# DFTT.net
KiCad netlist of a schematic drawn in EAGLE
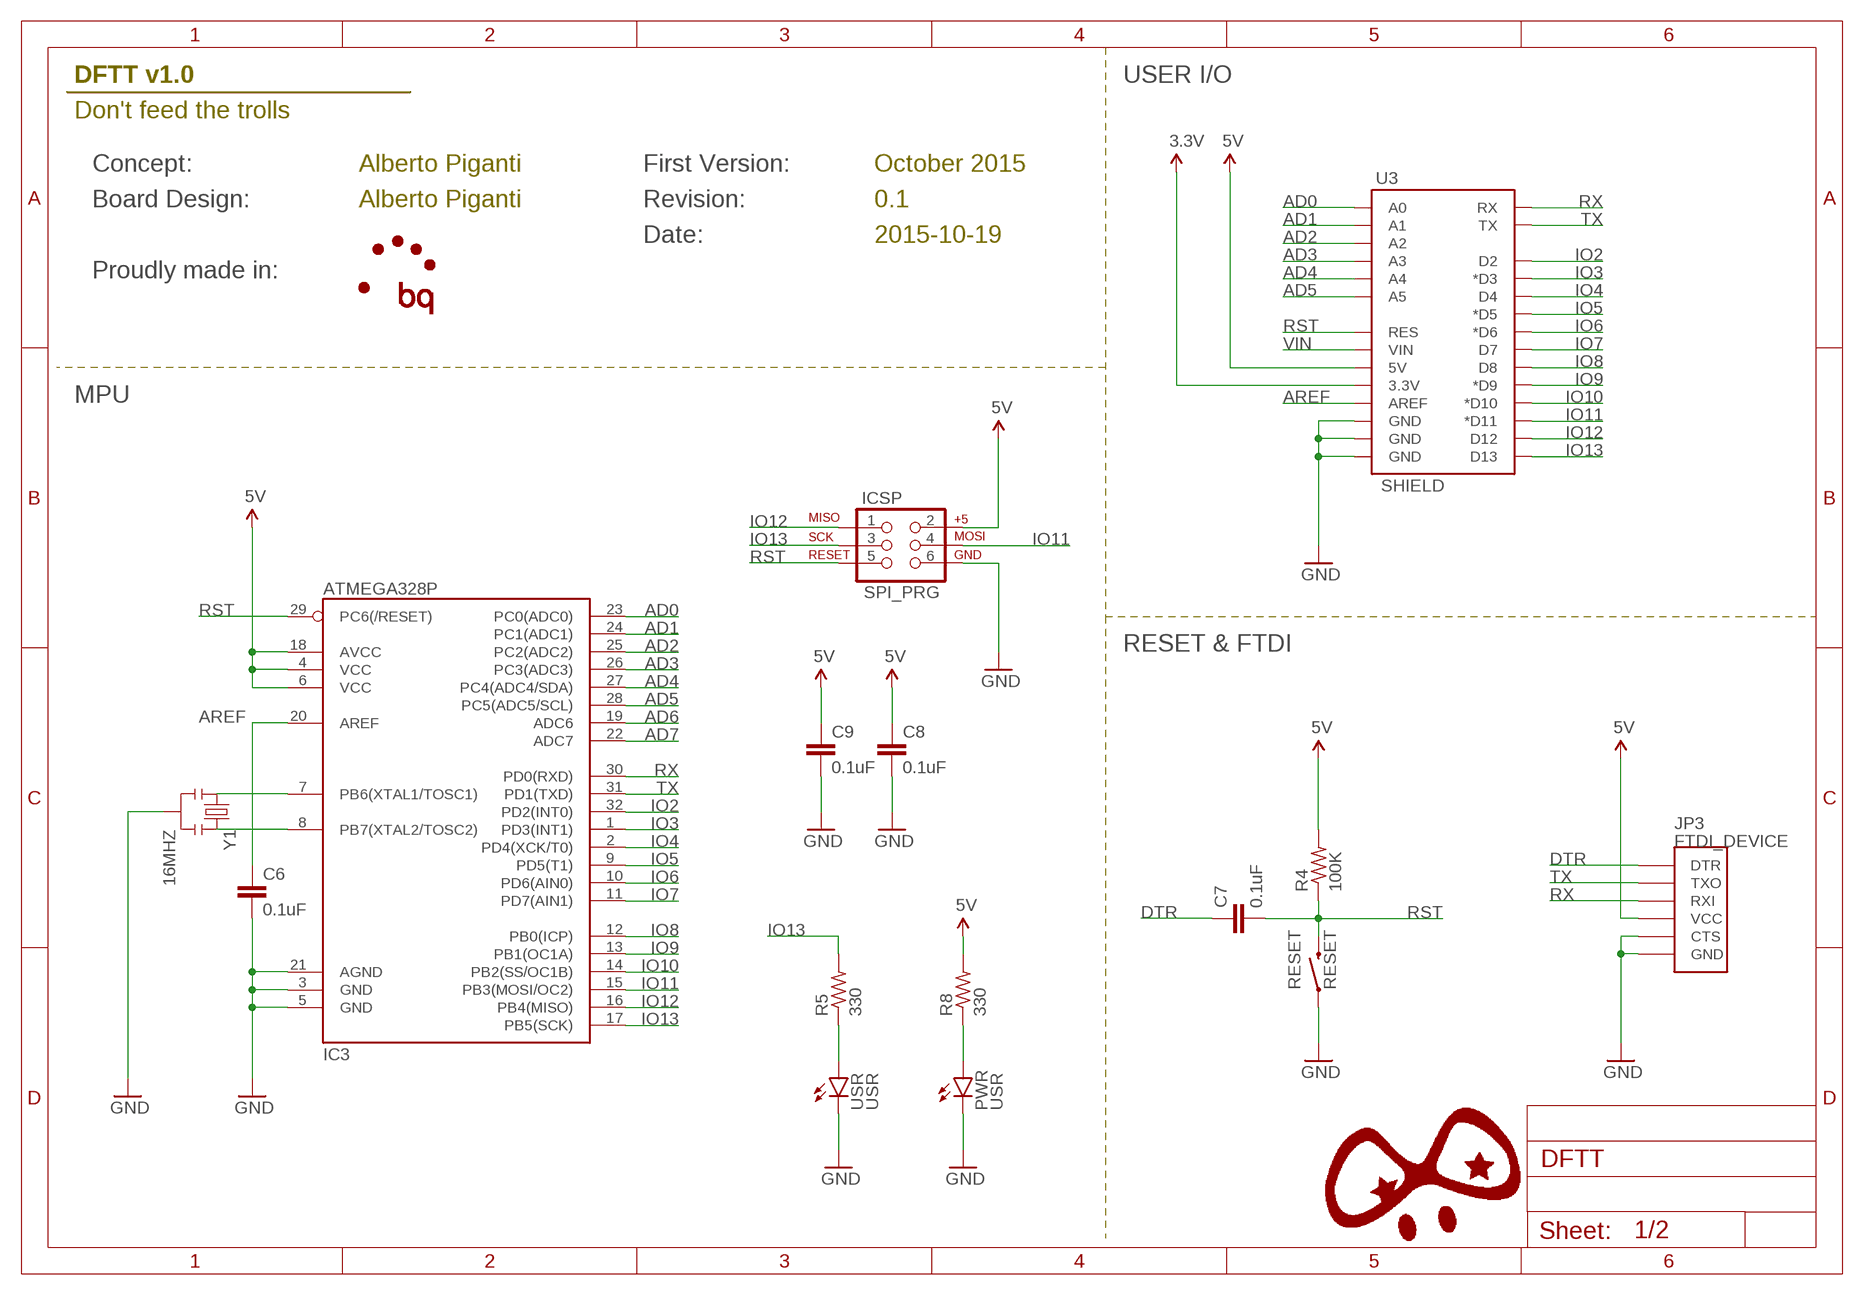
[diagram p0: schematic, sheet 1]
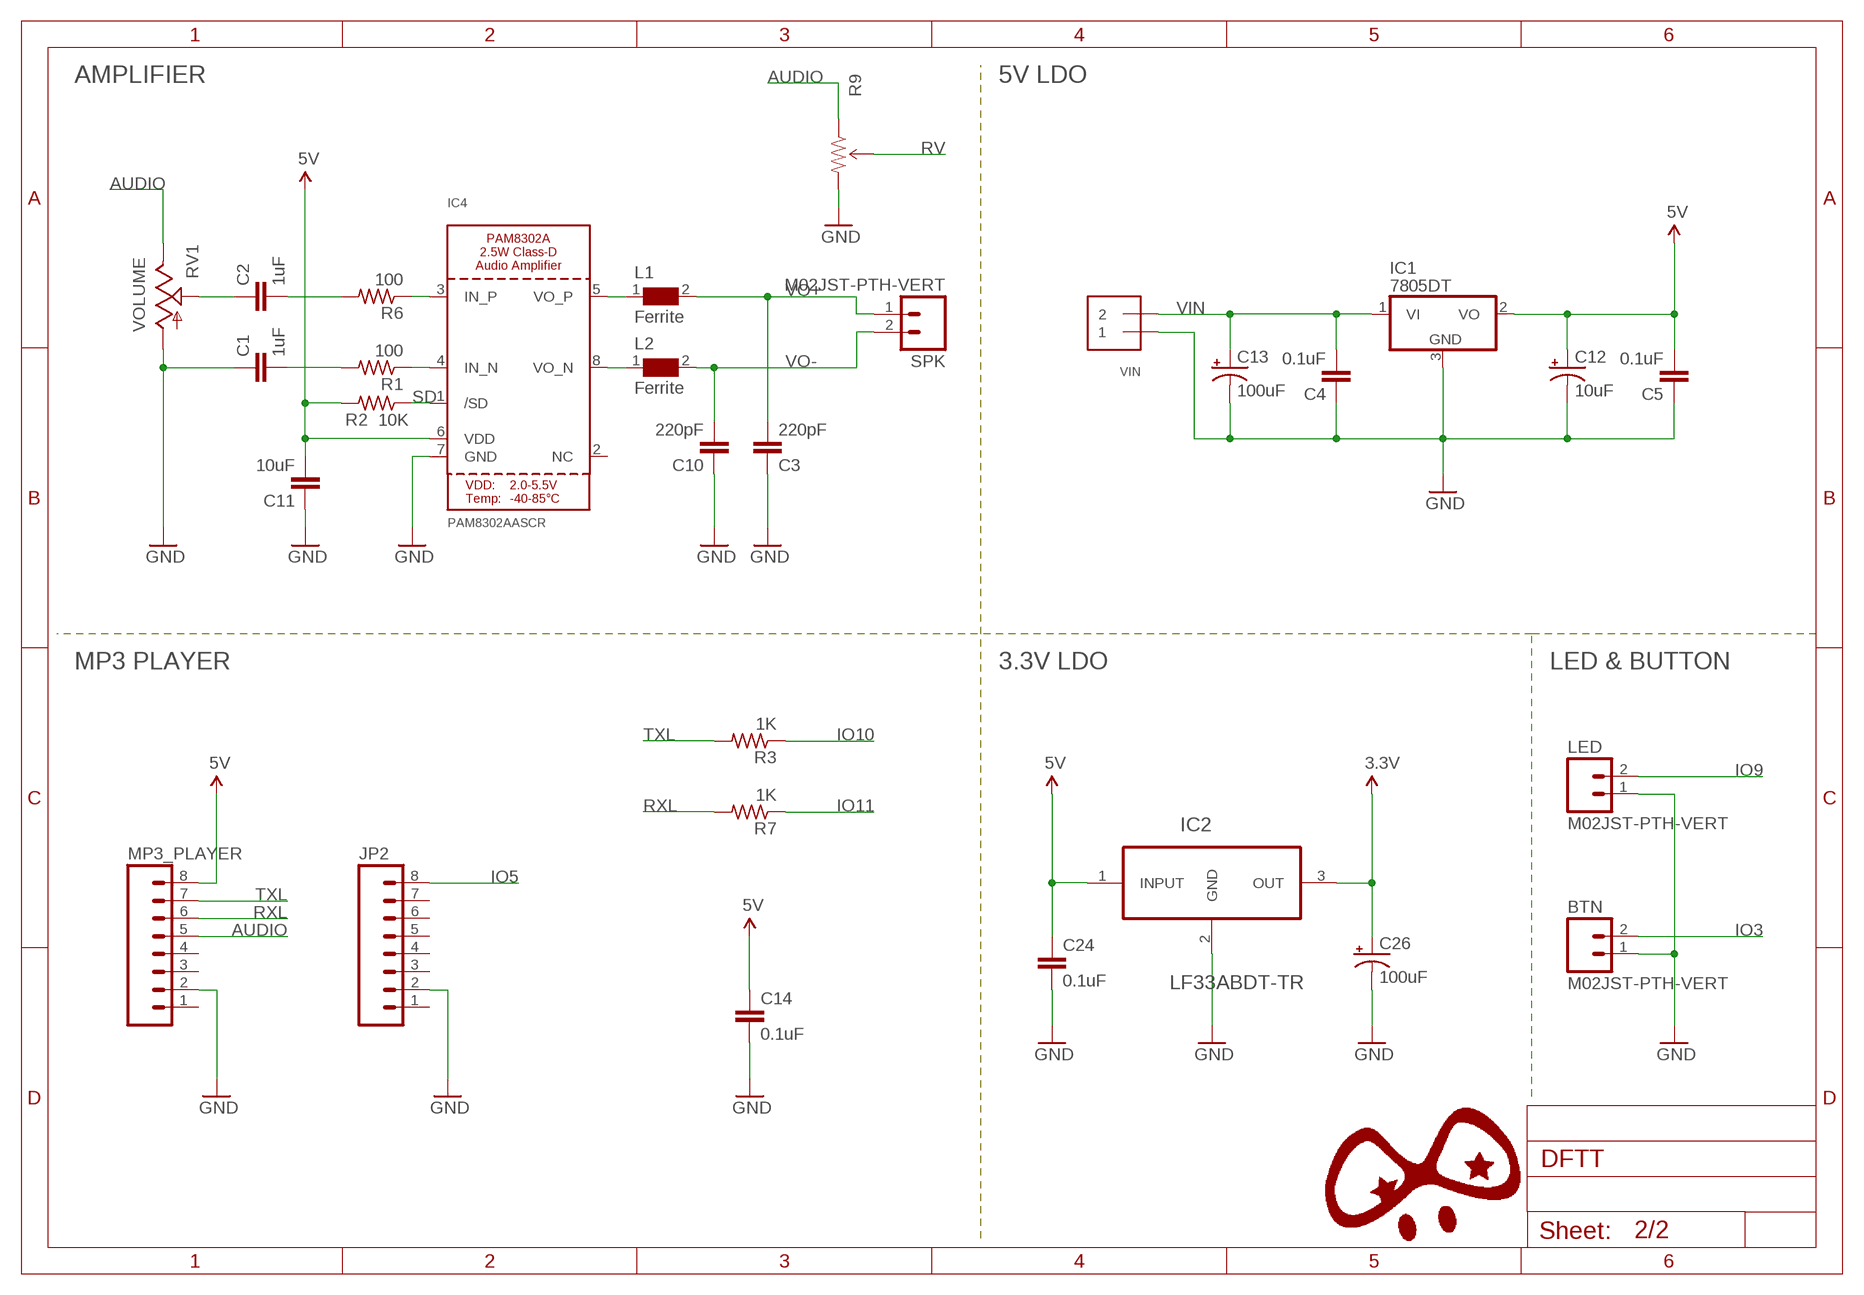
[diagram p1: schematic, sheet 2]

(export (version "E")
  (design (tool "Eeschema 10.0.6"))
  (components
    (comp (ref "BTN")
      (value "M02JST-PTH-VERT")
      (footprint "eagle-import:JST-2-PTH-VERT")
      (libsource (lib "eagle-import") (part "M02JST-PTH-VERT"))
    )
    (comp (ref "C1")
      (value "1uF")
      (footprint "eagle-import:C0603")
      (libsource (lib "eagle-import") (part "C-EUC0603"))
    )
    (comp (ref "C2")
      (value "1uF")
      (footprint "eagle-import:C0603")
      (libsource (lib "eagle-import") (part "C-EUC0603"))
    )
    (comp (ref "C3")
      (value "220pF")
      (footprint "eagle-import:C0603")
      (libsource (lib "eagle-import") (part "C-EUC0603"))
    )
    (comp (ref "C4")
      (value "0.1uF")
      (footprint "eagle-import:C0603")
      (libsource (lib "eagle-import") (part "C-EUC0603"))
    )
    (comp (ref "C5")
      (value "0.1uF")
      (footprint "eagle-import:C0603")
      (libsource (lib "eagle-import") (part "C-EUC0603"))
    )
    (comp (ref "C10")
      (value "220pF")
      (footprint "eagle-import:C0603")
      (libsource (lib "eagle-import") (part "C-EUC0603"))
    )
    (comp (ref "C11")
      (value "10uF")
      (footprint "eagle-import:C0603")
      (libsource (lib "eagle-import") (part "C-EUC0603"))
    )
    (comp (ref "C12")
      (value "10uF")
      (footprint "eagle-import:PANASONIC_D")
      (libsource (lib "eagle-import") (part "CAP_POLD"))
    )
    (comp (ref "C13")
      (value "100uF")
      (footprint "eagle-import:PANASONIC_D")
      (libsource (lib "eagle-import") (part "CAP_POLD"))
    )
    (comp (ref "C14")
      (value "0.1uF")
      (footprint "eagle-import:1210")
      (libsource (lib "eagle-import") (part "CAP1210"))
    )
    (comp (ref "C24")
      (value "0.1uF")
      (footprint "eagle-import:1210")
      (libsource (lib "eagle-import") (part "CAP1210"))
    )
    (comp (ref "C26")
      (value "100uF")
      (footprint "eagle-import:PANASONIC_D")
      (libsource (lib "eagle-import") (part "CAP_POLD"))
    )
    (comp (ref "IC1")
      (value "7805DT")
      (footprint "eagle-import:TO252")
      (libsource (lib "eagle-import") (part "78DT05"))
    )
    (comp (ref "IC2")
      (value "LF33ABDT-TR")
      (footprint "eagle-import:TO228P972X240-3N")
      (libsource (lib "eagle-import") (part "LF33ABDT-TR"))
    )
    (comp (ref "IC4")
      (value "PAM8302AASCR")
      (footprint "eagle-import:MSOP8_0.65MM")
      (libsource (lib "eagle-import") (part "AUDIOAMP_PAM8302A"))
    )
    (comp (ref "JP2")
      (value "M08LOCK")
      (footprint "eagle-import:1X08_LOCK")
      (libsource (lib "eagle-import") (part "M08LOCK"))
    )
    (comp (ref "L1")
      (value "Ferrite")
      (footprint "eagle-import:0603")
      (fields (field (name "MPN") "74279261"))
      (libsource (lib "eagle-import") (part "FERRITE_0603-74279261"))
    )
    (comp (ref "L2")
      (value "Ferrite")
      (footprint "eagle-import:0603")
      (fields (field (name "MPN") "74279261"))
      (libsource (lib "eagle-import") (part "FERRITE_0603-74279261"))
    )
    (comp (ref "LED")
      (value "M02JST-PTH-VERT")
      (footprint "eagle-import:JST-2-PTH-VERT")
      (libsource (lib "eagle-import") (part "M02JST-PTH-VERT"))
    )
    (comp (ref "MP3_PLAYER")
      (value "M08LOCK")
      (footprint "eagle-import:1X08_LOCK")
      (libsource (lib "eagle-import") (part "M08LOCK"))
    )
    (comp (ref "R1")
      (value "100")
      (footprint "eagle-import:R0603")
      (libsource (lib "eagle-import") (part "R-US_R0603"))
    )
    (comp (ref "R2")
      (value "10K")
      (footprint "eagle-import:R0603")
      (libsource (lib "eagle-import") (part "R-US_R0603"))
    )
    (comp (ref "R3")
      (value "1K")
      (footprint "eagle-import:R0603")
      (libsource (lib "eagle-import") (part "R-US_R0603"))
    )
    (comp (ref "R6")
      (value "100")
      (footprint "eagle-import:R0603")
      (libsource (lib "eagle-import") (part "R-US_R0603"))
    )
    (comp (ref "R7")
      (value "1K")
      (footprint "eagle-import:R0603")
      (libsource (lib "eagle-import") (part "R-US_R0603"))
    )
    (comp (ref "R9")
      (value "TRIMPOT3362U-2")
      (footprint "eagle-import:3362U-2")
      (libsource (lib "eagle-import") (part "TRIMPOT3362U-2"))
    )
    (comp (ref "RV1")
      (value "VOLUME")
      (footprint "eagle-import:TRIM_POT")
      (libsource (lib "eagle-import") (part "POTTRIM"))
    )
    (comp (ref "SPK")
      (value "M02JST-PTH-VERT")
      (footprint "eagle-import:JST-2-PTH-VERT")
      (libsource (lib "eagle-import") (part "M02JST-PTH-VERT"))
    )
    (comp (ref "VIN")
      (value "TERMBLOCK_1X2")
      (footprint "eagle-import:TERMBLOCK_1X2-3.5MM")
      (libsource (lib "eagle-import") (part "TERMBLOCK_1X2"))
    )
    (comp (ref "C6")
      (value "0.1uF")
      (footprint "eagle-import:C0603")
      (libsource (lib "eagle-import") (part "C-EUC0603"))
    )
    (comp (ref "C7")
      (value "0.1uF")
      (footprint "eagle-import:C0603")
      (libsource (lib "eagle-import") (part "C-EUC0603"))
    )
    (comp (ref "C8")
      (value "0.1uF")
      (footprint "eagle-import:C0603")
      (libsource (lib "eagle-import") (part "C-EUC0603"))
    )
    (comp (ref "C9")
      (value "0.1uF")
      (footprint "eagle-import:C0603")
      (libsource (lib "eagle-import") (part "C-EUC0603"))
    )
    (comp (ref "IC3")
      (value "ATMEGA328P")
      (footprint "eagle-import:TQFP32-08")
      (libsource (lib "eagle-import") (part "ATMEGA328_SMT"))
    )
    (comp (ref "ICSP")
      (value "SPI_PRG")
      (footprint "eagle-import:2X3-NS")
      (libsource (lib "eagle-import") (part "AVR_SPI_PRG_6NS"))
    )
    (comp (ref "JP3")
      (value "FTDI_DEVICE")
      (footprint "eagle-import:FTDI_DEVICE_SIDE")
      (libsource (lib "eagle-import") (part "FTDI_DEVICE"))
    )
    (comp (ref "PWR")
      (value "USR")
      (footprint "eagle-import:LED-0603")
      (libsource (lib "eagle-import") (part "LED0603"))
    )
    (comp (ref "R4")
      (value "100K")
      (footprint "eagle-import:R0603")
      (libsource (lib "eagle-import") (part "R-US_R0603"))
    )
    (comp (ref "R5")
      (value "330")
      (footprint "eagle-import:R0603")
      (libsource (lib "eagle-import") (part "R-US_R0603"))
    )
    (comp (ref "R8")
      (value "330")
      (footprint "eagle-import:R0603")
      (libsource (lib "eagle-import") (part "R-US_R0603"))
    )
    (comp (ref "RESET")
      (value "RESET")
      (footprint "eagle-import:TACTILE-SWITCH-1101NE")
      (libsource (lib "eagle-import") (part "SWITCH-MOMENTARY-2SMD-1101NE"))
    )
    (comp (ref "U3")
      (value "SHIELD")
      (footprint "eagle-import:DUEMILANOVE_VIAS")
      (libsource (lib "eagle-import") (part "ARDUINO_SHIELDNO_SILK"))
    )
    (comp (ref "USR")
      (value "USR")
      (footprint "eagle-import:LED-0603")
      (libsource (lib "eagle-import") (part "LED0603"))
    )
    (comp (ref "Y1")
      (value "16MHZ")
      (footprint "eagle-import:RESONATOR-SMD")
      (libsource (lib "eagle-import") (part "RESONATOR16MHZ"))
    )
  )
  (nets
    (net (code "1") (name "3.3V") (class "Default")
      (node (ref "C26") (pin "+") (pinfunction "+_+") (pintype "passive"))
      (node (ref "IC2") (pin "3") (pinfunction "OUT_3") (pintype "output"))
      (node (ref "U3") (pin "3.3V") (pinfunction "3.3V_3.3V") (pintype "bidirectional"))
    )
    (net (code "2") (name "5V") (class "Default")
      (node (ref "C11") (pin "2") (pinfunction "2_2") (pintype "passive"))
      (node (ref "C12") (pin "+") (pinfunction "+_+") (pintype "passive"))
      (node (ref "C14") (pin "1") (pinfunction "1_1") (pintype "passive"))
      (node (ref "C24") (pin "1") (pinfunction "1_1") (pintype "passive"))
      (node (ref "C5") (pin "2") (pinfunction "2_2") (pintype "passive"))
      (node (ref "C8") (pin "1") (pinfunction "1_1") (pintype "passive"))
      (node (ref "C9") (pin "1") (pinfunction "1_1") (pintype "passive"))
      (node (ref "IC1") (pin "2") (pinfunction "VO_2") (pintype "passive"))
      (node (ref "IC2") (pin "1") (pinfunction "INPUT_1") (pintype "input"))
      (node (ref "IC3") (pin "18") (pinfunction "AVCC_18") (pintype "bidirectional"))
      (node (ref "IC3") (pin "4") (pinfunction "VCC_4") (pintype "bidirectional"))
      (node (ref "IC3") (pin "6") (pinfunction "VCC_6") (pintype "bidirectional"))
      (node (ref "IC4") (pin "6") (pinfunction "VDD_6") (pintype "power_in"))
      (node (ref "ICSP") (pin "2") (pinfunction "2_2") (pintype "passive"))
      (node (ref "JP3") (pin "P$4") (pinfunction "VCC_P$4") (pintype "bidirectional"))
      (node (ref "MP3_PLAYER") (pin "8") (pinfunction "8_8") (pintype "passive"))
      (node (ref "R2") (pin "2") (pinfunction "2_2") (pintype "passive"))
      (node (ref "R4") (pin "2") (pinfunction "2_2") (pintype "passive"))
      (node (ref "R8") (pin "2") (pinfunction "2_2") (pintype "passive"))
      (node (ref "U3") (pin "5V") (pinfunction "5V_5V") (pintype "bidirectional"))
    )
    (net (code "3") (name "AD0") (class "Default")
      (node (ref "IC3") (pin "23") (pinfunction "PC0(ADC0)_23") (pintype "bidirectional"))
      (node (ref "U3") (pin "A0") (pinfunction "A0_A0") (pintype "bidirectional"))
    )
    (net (code "4") (name "AD1") (class "Default")
      (node (ref "IC3") (pin "24") (pinfunction "PC1(ADC1)_24") (pintype "bidirectional"))
      (node (ref "U3") (pin "A1") (pinfunction "A1_A1") (pintype "bidirectional"))
    )
    (net (code "5") (name "AD2") (class "Default")
      (node (ref "IC3") (pin "25") (pinfunction "PC2(ADC2)_25") (pintype "bidirectional"))
      (node (ref "U3") (pin "A2") (pinfunction "A2_A2") (pintype "bidirectional"))
    )
    (net (code "6") (name "AD3") (class "Default")
      (node (ref "IC3") (pin "26") (pinfunction "PC3(ADC3)_26") (pintype "bidirectional"))
      (node (ref "U3") (pin "A3") (pinfunction "A3_A3") (pintype "bidirectional"))
    )
    (net (code "7") (name "AD4") (class "Default")
      (node (ref "IC3") (pin "27") (pinfunction "PC4(ADC4/SDA)_27") (pintype "bidirectional"))
      (node (ref "U3") (pin "A4") (pinfunction "A4_A4") (pintype "bidirectional"))
    )
    (net (code "8") (name "AD5") (class "Default")
      (node (ref "IC3") (pin "28") (pinfunction "PC5(ADC5/SCL)_28") (pintype "bidirectional"))
      (node (ref "U3") (pin "A5") (pinfunction "A5_A5") (pintype "bidirectional"))
    )
    (net (code "9") (name "AD6") (class "Default")
      (node (ref "IC3") (pin "19") (pinfunction "ADC6_19") (pintype "bidirectional"))
    )
    (net (code "10") (name "AD7") (class "Default")
      (node (ref "IC3") (pin "22") (pinfunction "ADC7_22") (pintype "bidirectional"))
    )
    (net (code "11") (name "AREF") (class "Default")
      (node (ref "C6") (pin "1") (pinfunction "1_1") (pintype "passive"))
      (node (ref "IC3") (pin "20") (pinfunction "AREF_20") (pintype "bidirectional"))
      (node (ref "U3") (pin "AREF") (pinfunction "AREF_AREF") (pintype "bidirectional"))
    )
    (net (code "12") (name "AUDIO") (class "Default")
      (node (ref "MP3_PLAYER") (pin "5") (pinfunction "5_5") (pintype "passive"))
      (node (ref "R9") (pin "1") (pinfunction "CCW_1") (pintype "passive"))
      (node (ref "RV1") (pin "2") (pinfunction "E_2") (pintype "passive"))
    )
    (net (code "13") (name "DTR") (class "Default")
      (node (ref "C7") (pin "1") (pinfunction "1_1") (pintype "passive"))
      (node (ref "JP3") (pin "P$1") (pinfunction "DTR_P$1") (pintype "bidirectional"))
    )
    (net (code "14") (name "GND") (class "Default")
      (node (ref "BTN") (pin "1") (pinfunction "1_1") (pintype "passive"))
      (node (ref "C1") (pin "1") (pinfunction "1_1") (pintype "passive"))
      (node (ref "C10") (pin "1") (pinfunction "1_1") (pintype "passive"))
      (node (ref "C11") (pin "1") (pinfunction "1_1") (pintype "passive"))
      (node (ref "C12") (pin "-") (pinfunction "-_-") (pintype "passive"))
      (node (ref "C13") (pin "-") (pinfunction "-_-") (pintype "passive"))
      (node (ref "C14") (pin "2") (pinfunction "2_2") (pintype "passive"))
      (node (ref "C24") (pin "2") (pinfunction "2_2") (pintype "passive"))
      (node (ref "C26") (pin "-") (pinfunction "-_-") (pintype "passive"))
      (node (ref "C3") (pin "1") (pinfunction "1_1") (pintype "passive"))
      (node (ref "C4") (pin "1") (pinfunction "1_1") (pintype "passive"))
      (node (ref "C5") (pin "1") (pinfunction "1_1") (pintype "passive"))
      (node (ref "C6") (pin "2") (pinfunction "2_2") (pintype "passive"))
      (node (ref "C8") (pin "2") (pinfunction "2_2") (pintype "passive"))
      (node (ref "C9") (pin "2") (pinfunction "2_2") (pintype "passive"))
      (node (ref "IC1") (pin "3") (pinfunction "GND_3") (pintype "passive"))
      (node (ref "IC2") (pin "2") (pinfunction "GND_2") (pintype "passive"))
      (node (ref "IC3") (pin "21") (pinfunction "AGND_21") (pintype "bidirectional"))
      (node (ref "IC3") (pin "3") (pinfunction "GND_3") (pintype "bidirectional"))
      (node (ref "IC3") (pin "5") (pinfunction "GND_5") (pintype "bidirectional"))
      (node (ref "IC4") (pin "7") (pinfunction "GND_7") (pintype "power_in"))
      (node (ref "ICSP") (pin "6") (pinfunction "6_6") (pintype "passive"))
      (node (ref "JP2") (pin "2") (pinfunction "2_2") (pintype "passive"))
      (node (ref "JP3") (pin "P$5") (pinfunction "CTS_P$5") (pintype "bidirectional"))
      (node (ref "JP3") (pin "P$6") (pinfunction "GND_P$6") (pintype "bidirectional"))
      (node (ref "LED") (pin "1") (pinfunction "1_1") (pintype "passive"))
      (node (ref "MP3_PLAYER") (pin "2") (pinfunction "2_2") (pintype "passive"))
      (node (ref "PWR") (pin "C") (pinfunction "C_C") (pintype "passive"))
      (node (ref "R9") (pin "3") (pinfunction "CW_3") (pintype "passive"))
      (node (ref "RESET") (pin "1") (pinfunction "1_1") (pintype "passive"))
      (node (ref "RV1") (pin "3") (pinfunction "A_3") (pintype "passive"))
      (node (ref "U3") (pin "GND@0") (pinfunction "GND_GND@0") (pintype "bidirectional"))
      (node (ref "U3") (pin "GND@1") (pinfunction "GND_GND@1") (pintype "bidirectional"))
      (node (ref "U3") (pin "GND@2") (pinfunction "GND_GND@2") (pintype "bidirectional"))
      (node (ref "USR") (pin "C") (pinfunction "C_C") (pintype "passive"))
      (node (ref "VIN") (pin "1") (pinfunction "1_1") (pintype "passive"))
      (node (ref "Y1") (pin "2") (pinfunction "2_2") (pintype "passive"))
    )
    (net (code "15") (name "IO2") (class "Default")
      (node (ref "IC3") (pin "32") (pinfunction "PD2(INT0)_32") (pintype "bidirectional"))
      (node (ref "U3") (pin "D2") (pinfunction "D2_D2") (pintype "bidirectional"))
    )
    (net (code "16") (name "IO3") (class "Default")
      (node (ref "BTN") (pin "2") (pinfunction "2_2") (pintype "passive"))
      (node (ref "IC3") (pin "1") (pinfunction "PD3(INT1)_1") (pintype "bidirectional"))
      (node (ref "U3") (pin "D3") (pinfunction "*D3_D3") (pintype "bidirectional"))
    )
    (net (code "17") (name "IO4") (class "Default")
      (node (ref "IC3") (pin "2") (pinfunction "PD4(XCK/T0)_2") (pintype "bidirectional"))
      (node (ref "U3") (pin "D4") (pinfunction "D4_D4") (pintype "bidirectional"))
    )
    (net (code "18") (name "IO5") (class "Default")
      (node (ref "IC3") (pin "9") (pinfunction "PD5(T1)_9") (pintype "bidirectional"))
      (node (ref "JP2") (pin "8") (pinfunction "8_8") (pintype "passive"))
      (node (ref "U3") (pin "D5") (pinfunction "*D5_D5") (pintype "bidirectional"))
    )
    (net (code "19") (name "IO6") (class "Default")
      (node (ref "IC3") (pin "10") (pinfunction "PD6(AIN0)_10") (pintype "bidirectional"))
      (node (ref "U3") (pin "D6") (pinfunction "*D6_D6") (pintype "bidirectional"))
    )
    (net (code "20") (name "IO7") (class "Default")
      (node (ref "IC3") (pin "11") (pinfunction "PD7(AIN1)_11") (pintype "bidirectional"))
      (node (ref "U3") (pin "D7") (pinfunction "D7_D7") (pintype "bidirectional"))
    )
    (net (code "21") (name "IO8") (class "Default")
      (node (ref "IC3") (pin "12") (pinfunction "PB0(ICP)_12") (pintype "bidirectional"))
      (node (ref "U3") (pin "D8") (pinfunction "D8_D8") (pintype "bidirectional"))
    )
    (net (code "22") (name "IO9") (class "Default")
      (node (ref "IC3") (pin "13") (pinfunction "PB1(OC1A)_13") (pintype "bidirectional"))
      (node (ref "LED") (pin "2") (pinfunction "2_2") (pintype "passive"))
      (node (ref "U3") (pin "D9") (pinfunction "*D9_D9") (pintype "bidirectional"))
    )
    (net (code "23") (name "IO10") (class "Default")
      (node (ref "IC3") (pin "14") (pinfunction "PB2(SS/OC1B)_14") (pintype "bidirectional"))
      (node (ref "R3") (pin "1") (pinfunction "1_1") (pintype "passive"))
      (node (ref "U3") (pin "D10") (pinfunction "*D10_D10") (pintype "bidirectional"))
    )
    (net (code "24") (name "IO11") (class "Default")
      (node (ref "IC3") (pin "15") (pinfunction "PB3(MOSI/OC2)_15") (pintype "bidirectional"))
      (node (ref "ICSP") (pin "4") (pinfunction "4_4") (pintype "passive"))
      (node (ref "R7") (pin "1") (pinfunction "1_1") (pintype "passive"))
      (node (ref "U3") (pin "D11") (pinfunction "*D11_D11") (pintype "bidirectional"))
    )
    (net (code "25") (name "IO12") (class "Default")
      (node (ref "IC3") (pin "16") (pinfunction "PB4(MISO)_16") (pintype "bidirectional"))
      (node (ref "ICSP") (pin "1") (pinfunction "1_1") (pintype "passive"))
      (node (ref "U3") (pin "D12") (pinfunction "D12_D12") (pintype "bidirectional"))
    )
    (net (code "26") (name "IO13") (class "Default")
      (node (ref "IC3") (pin "17") (pinfunction "PB5(SCK)_17") (pintype "bidirectional"))
      (node (ref "ICSP") (pin "3") (pinfunction "3_3") (pintype "passive"))
      (node (ref "R5") (pin "2") (pinfunction "2_2") (pintype "passive"))
      (node (ref "U3") (pin "D13") (pinfunction "D13_D13") (pintype "bidirectional"))
    )
    (net (code "27") (name "Net-(C1-Pad2)") (class "Default")
      (node (ref "C1") (pin "2") (pinfunction "2_2") (pintype "passive"))
      (node (ref "R1") (pin "2") (pinfunction "2_2") (pintype "passive"))
    )
    (net (code "28") (name "Net-(C2-Pad2)") (class "Default")
      (node (ref "C2") (pin "2") (pinfunction "2_2") (pintype "passive"))
      (node (ref "R6") (pin "2") (pinfunction "2_2") (pintype "passive"))
    )
    (net (code "29") (name "Net-(IC3-PB6(XTAL1{slash}TOSC1))") (class "Default")
      (node (ref "IC3") (pin "7") (pinfunction "PB6(XTAL1/TOSC1)_7") (pintype "bidirectional"))
      (node (ref "Y1") (pin "1") (pinfunction "1_1") (pintype "passive"))
    )
    (net (code "30") (name "Net-(IC3-PB7(XTAL2{slash}TOSC2))") (class "Default")
      (node (ref "IC3") (pin "8") (pinfunction "PB7(XTAL2/TOSC2)_8") (pintype "bidirectional"))
      (node (ref "Y1") (pin "3") (pinfunction "3_3") (pintype "passive"))
    )
    (net (code "31") (name "Net-(IC4-IN_N)") (class "Default")
      (node (ref "IC4") (pin "4") (pinfunction "IN_N_4") (pintype "input"))
      (node (ref "R1") (pin "1") (pinfunction "1_1") (pintype "passive"))
    )
    (net (code "32") (name "Net-(IC4-IN_P)") (class "Default")
      (node (ref "IC4") (pin "3") (pinfunction "IN_P_3") (pintype "input"))
      (node (ref "R6") (pin "1") (pinfunction "1_1") (pintype "passive"))
    )
    (net (code "33") (name "Net-(IC4-VO_N)") (class "Default")
      (node (ref "IC4") (pin "8") (pinfunction "VO_N_8") (pintype "output"))
      (node (ref "L2") (pin "1") (pinfunction "1_1") (pintype "passive"))
    )
    (net (code "34") (name "Net-(IC4-VO_P)") (class "Default")
      (node (ref "IC4") (pin "5") (pinfunction "VO_P_5") (pintype "output"))
      (node (ref "L1") (pin "1") (pinfunction "1_1") (pintype "passive"))
    )
    (net (code "35") (name "Net-(PWR-PadA)") (class "Default")
      (node (ref "PWR") (pin "A") (pinfunction "A_A") (pintype "passive"))
      (node (ref "R8") (pin "1") (pinfunction "1_1") (pintype "passive"))
    )
    (net (code "36") (name "Net-(R5-Pad1)") (class "Default")
      (node (ref "R5") (pin "1") (pinfunction "1_1") (pintype "passive"))
      (node (ref "USR") (pin "A") (pinfunction "A_A") (pintype "passive"))
    )
    (net (code "37") (name "RST") (class "Default")
      (node (ref "C7") (pin "2") (pinfunction "2_2") (pintype "passive"))
      (node (ref "IC3") (pin "29") (pinfunction "PC6(/RESET)_29") (pintype "bidirectional"))
      (node (ref "ICSP") (pin "5") (pinfunction "5_5") (pintype "passive"))
      (node (ref "R4") (pin "1") (pinfunction "1_1") (pintype "passive"))
      (node (ref "RESET") (pin "2") (pinfunction "2_2") (pintype "passive"))
      (node (ref "U3") (pin "RES") (pinfunction "RES_RES") (pintype "bidirectional"))
    )
    (net (code "38") (name "RV") (class "Default")
      (node (ref "C2") (pin "1") (pinfunction "1_1") (pintype "passive"))
      (node (ref "R9") (pin "2") (pinfunction "WIPER_2") (pintype "passive"))
      (node (ref "RV1") (pin "1") (pinfunction "S_1") (pintype "passive"))
    )
    (net (code "39") (name "RX") (class "Default")
      (node (ref "IC3") (pin "30") (pinfunction "PD0(RXD)_30") (pintype "bidirectional"))
      (node (ref "JP3") (pin "P$3") (pinfunction "RXI_P$3") (pintype "bidirectional"))
      (node (ref "U3") (pin "RX") (pinfunction "RX_RX") (pintype "bidirectional"))
    )
    (net (code "40") (name "RXL") (class "Default")
      (node (ref "MP3_PLAYER") (pin "6") (pinfunction "6_6") (pintype "passive"))
      (node (ref "R7") (pin "2") (pinfunction "2_2") (pintype "passive"))
    )
    (net (code "41") (name "SD") (class "Default")
      (node (ref "IC4") (pin "1") (pinfunction "/SD_1") (pintype "input"))
      (node (ref "R2") (pin "1") (pinfunction "1_1") (pintype "passive"))
    )
    (net (code "42") (name "TX") (class "Default")
      (node (ref "IC3") (pin "31") (pinfunction "PD1(TXD)_31") (pintype "bidirectional"))
      (node (ref "JP3") (pin "P$2") (pinfunction "TXO_P$2") (pintype "bidirectional"))
      (node (ref "U3") (pin "TX") (pinfunction "TX_TX") (pintype "bidirectional"))
    )
    (net (code "43") (name "TXL") (class "Default")
      (node (ref "MP3_PLAYER") (pin "7") (pinfunction "7_7") (pintype "passive"))
      (node (ref "R3") (pin "2") (pinfunction "2_2") (pintype "passive"))
    )
    (net (code "44") (name "VIN") (class "Default")
      (node (ref "C13") (pin "+") (pinfunction "+_+") (pintype "passive"))
      (node (ref "C4") (pin "2") (pinfunction "2_2") (pintype "passive"))
      (node (ref "IC1") (pin "1") (pinfunction "VI_1") (pintype "input"))
      (node (ref "U3") (pin "VIN") (pinfunction "VIN_VIN") (pintype "bidirectional"))
      (node (ref "VIN") (pin "2") (pinfunction "2_2") (pintype "passive"))
    )
    (net (code "45") (name "VO+") (class "Default")
      (node (ref "C3") (pin "2") (pinfunction "2_2") (pintype "passive"))
      (node (ref "L1") (pin "2") (pinfunction "2_2") (pintype "passive"))
      (node (ref "SPK") (pin "1") (pinfunction "1_1") (pintype "passive"))
    )
    (net (code "46") (name "VO-") (class "Default")
      (node (ref "C10") (pin "2") (pinfunction "2_2") (pintype "passive"))
      (node (ref "L2") (pin "2") (pinfunction "2_2") (pintype "passive"))
      (node (ref "SPK") (pin "2") (pinfunction "2_2") (pintype "passive"))
    )
    (net (code "47") (name "unconnected-(IC4-NC-Pad2)") (class "Default")
      (node (ref "IC4") (pin "2") (pinfunction "NC_2") (pintype "no_connect"))
    )
    (net (code "48") (name "unconnected-(JP2-Pad1)") (class "Default")
      (node (ref "JP2") (pin "1") (pinfunction "1_1") (pintype "passive"))
    )
    (net (code "49") (name "unconnected-(JP2-Pad3)") (class "Default")
      (node (ref "JP2") (pin "3") (pinfunction "3_3") (pintype "passive"))
    )
    (net (code "50") (name "unconnected-(JP2-Pad4)") (class "Default")
      (node (ref "JP2") (pin "4") (pinfunction "4_4") (pintype "passive"))
    )
    (net (code "51") (name "unconnected-(JP2-Pad5)") (class "Default")
      (node (ref "JP2") (pin "5") (pinfunction "5_5") (pintype "passive"))
    )
    (net (code "52") (name "unconnected-(JP2-Pad6)") (class "Default")
      (node (ref "JP2") (pin "6") (pinfunction "6_6") (pintype "passive"))
    )
    (net (code "53") (name "unconnected-(JP2-Pad7)") (class "Default")
      (node (ref "JP2") (pin "7") (pinfunction "7_7") (pintype "passive"))
    )
    (net (code "54") (name "unconnected-(MP3_PLAYER-Pad1)") (class "Default")
      (node (ref "MP3_PLAYER") (pin "1") (pinfunction "1_1") (pintype "passive"))
    )
    (net (code "55") (name "unconnected-(MP3_PLAYER-Pad3)") (class "Default")
      (node (ref "MP3_PLAYER") (pin "3") (pinfunction "3_3") (pintype "passive"))
    )
    (net (code "56") (name "unconnected-(MP3_PLAYER-Pad4)") (class "Default")
      (node (ref "MP3_PLAYER") (pin "4") (pinfunction "4_4") (pintype "passive"))
    )
  )
)
